# FrontPanel-IN14.net
KiCad netlist of a schematic drawn in EAGLE
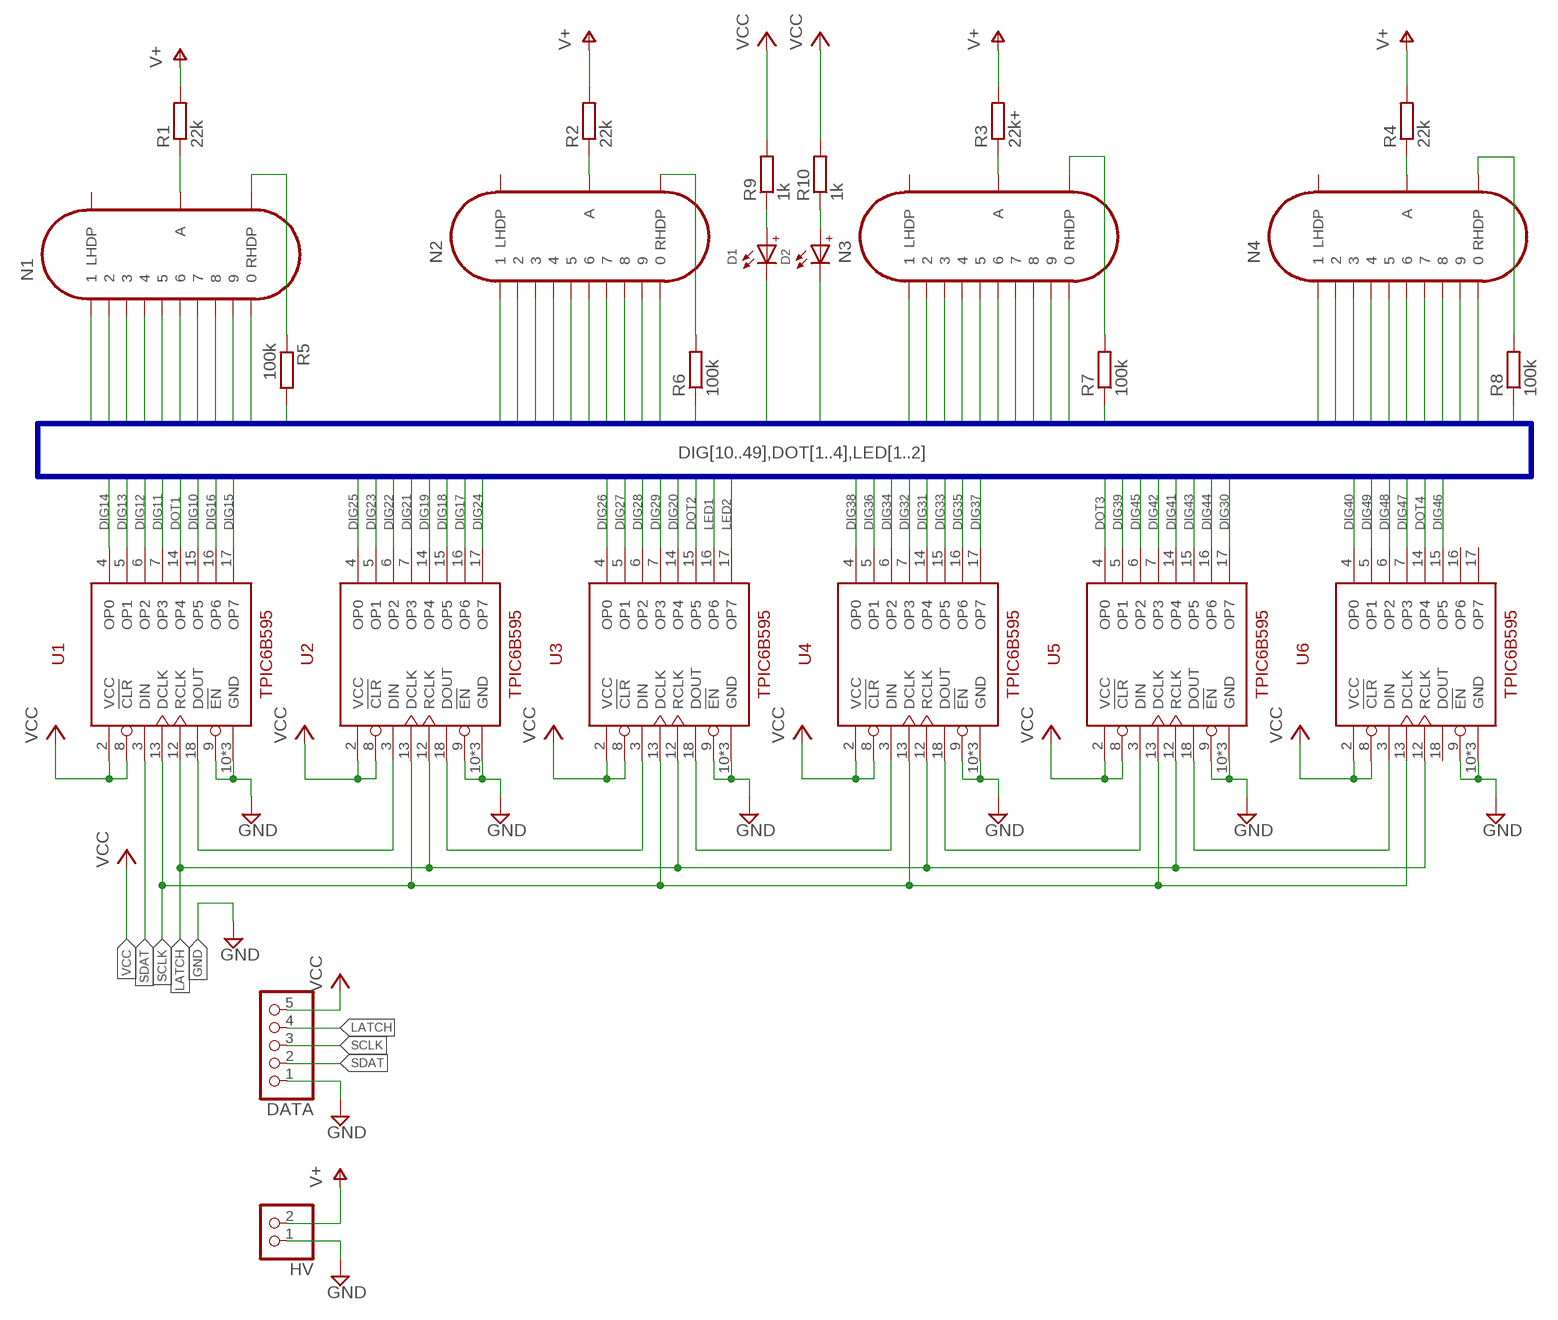
[diagram p0: schematic, sheet 1]

(export (version "E")
  (design (tool "Eeschema 10.0.6"))
  (components
    (comp (ref "D1")
      (value "RED/AMBER")
      (footprint "eagle-import:WL-SITW_154141XXBA210")
      (libsource (lib "eagle-import") (part "WL-SITW_3528_15414185BA210"))
    )
    (comp (ref "D2")
      (value "RED/AMBER")
      (footprint "eagle-import:WL-SITW_154141XXBA210")
      (libsource (lib "eagle-import") (part "WL-SITW_3528_15414185BA210"))
    )
    (comp (ref "DATA")
      (value ".1\" Header")
      (footprint "eagle-import:1X05")
      (libsource (lib "eagle-import") (part "PINHD-1X5"))
    )
    (comp (ref "HV")
      (value ".1\" Header")
      (footprint "eagle-import:1X02")
      (libsource (lib "eagle-import") (part "PINHD-1X2"))
    )
    (comp (ref "N1")
      (value "IN-14")
      (footprint "eagle-import:IN-14")
      (libsource (lib "eagle-import") (part "IN-14"))
    )
    (comp (ref "N2")
      (value "IN-14")
      (footprint "eagle-import:IN-14")
      (libsource (lib "eagle-import") (part "IN-14"))
    )
    (comp (ref "N3")
      (value "IN-14")
      (footprint "eagle-import:IN-14")
      (libsource (lib "eagle-import") (part "IN-14"))
    )
    (comp (ref "N4")
      (value "IN-14")
      (footprint "eagle-import:IN-14")
      (libsource (lib "eagle-import") (part "IN-14"))
    )
    (comp (ref "R1")
      (value "22k")
      (footprint "eagle-import:0207_10")
      (libsource (lib "eagle-import") (part "R-EU_0207/10"))
    )
    (comp (ref "R2")
      (value "22k")
      (footprint "eagle-import:0207_10")
      (libsource (lib "eagle-import") (part "R-EU_0207/10"))
    )
    (comp (ref "R3")
      (value "22k+")
      (footprint "eagle-import:0207_10")
      (libsource (lib "eagle-import") (part "R-EU_0207/10"))
    )
    (comp (ref "R4")
      (value "22k")
      (footprint "eagle-import:0207_10")
      (libsource (lib "eagle-import") (part "R-EU_0207/10"))
    )
    (comp (ref "R5")
      (value "100k")
      (footprint "eagle-import:0207_10")
      (libsource (lib "eagle-import") (part "R-EU_0207/10"))
    )
    (comp (ref "R6")
      (value "100k")
      (footprint "eagle-import:0207_10")
      (libsource (lib "eagle-import") (part "R-EU_0207/10"))
    )
    (comp (ref "R7")
      (value "100k")
      (footprint "eagle-import:0207_10")
      (libsource (lib "eagle-import") (part "R-EU_0207/10"))
    )
    (comp (ref "R8")
      (value "100k")
      (footprint "eagle-import:0207_10")
      (libsource (lib "eagle-import") (part "R-EU_0207/10"))
    )
    (comp (ref "R9")
      (value "1k")
      (footprint "eagle-import:0207_10")
      (libsource (lib "eagle-import") (part "R-EU_0207/10"))
    )
    (comp (ref "R10")
      (value "1k")
      (footprint "eagle-import:0207_10")
      (libsource (lib "eagle-import") (part "R-EU_0207/10"))
    )
    (comp (ref "U1")
      (value "TPIC6B595N")
      (footprint "eagle-import:PDIP-20")
      (libsource (lib "eagle-import") (part "TPIC6B595N"))
    )
    (comp (ref "U2")
      (value "TPIC6B595N")
      (footprint "eagle-import:PDIP-20")
      (libsource (lib "eagle-import") (part "TPIC6B595N"))
    )
    (comp (ref "U3")
      (value "TPIC6B595N")
      (footprint "eagle-import:PDIP-20")
      (libsource (lib "eagle-import") (part "TPIC6B595N"))
    )
    (comp (ref "U4")
      (value "TPIC6B595N")
      (footprint "eagle-import:PDIP-20")
      (libsource (lib "eagle-import") (part "TPIC6B595N"))
    )
    (comp (ref "U5")
      (value "TPIC6B595N")
      (footprint "eagle-import:PDIP-20")
      (libsource (lib "eagle-import") (part "TPIC6B595N"))
    )
    (comp (ref "U6")
      (value "TPIC6B595N")
      (footprint "eagle-import:PDIP-20")
      (libsource (lib "eagle-import") (part "TPIC6B595N"))
    )
  )
  (nets
    (net (code "1") (name "/DIG10") (class "Default")
      (node (ref "N1") (pin "0") (pinfunction "0_0") (pintype "bidirectional"))
      (node (ref "U1") (pin "15") (pinfunction "OP5_15") (pintype "open_collector"))
    )
    (net (code "2") (name "/DIG11") (class "Default")
      (node (ref "N1") (pin "1") (pinfunction "1_1") (pintype "bidirectional"))
      (node (ref "U1") (pin "7") (pinfunction "OP3_7") (pintype "open_collector"))
    )
    (net (code "3") (name "/DIG12") (class "Default")
      (node (ref "N1") (pin "2") (pinfunction "2_2") (pintype "bidirectional"))
      (node (ref "U1") (pin "6") (pinfunction "OP2_6") (pintype "open_collector"))
    )
    (net (code "4") (name "/DIG13") (class "Default")
      (node (ref "N1") (pin "3") (pinfunction "3_3") (pintype "bidirectional"))
      (node (ref "U1") (pin "5") (pinfunction "OP1_5") (pintype "open_collector"))
    )
    (net (code "5") (name "/DIG14") (class "Default")
      (node (ref "N1") (pin "4") (pinfunction "4_4") (pintype "bidirectional"))
      (node (ref "U1") (pin "4") (pinfunction "OP0_4") (pintype "open_collector"))
    )
    (net (code "6") (name "/DIG15") (class "Default")
      (node (ref "N1") (pin "5") (pinfunction "5_5") (pintype "bidirectional"))
      (node (ref "U1") (pin "17") (pinfunction "OP7_17") (pintype "open_collector"))
    )
    (net (code "7") (name "/DIG16") (class "Default")
      (node (ref "N1") (pin "6") (pinfunction "6_6") (pintype "bidirectional"))
      (node (ref "U1") (pin "16") (pinfunction "OP6_16") (pintype "open_collector"))
    )
    (net (code "8") (name "/DIG17") (class "Default")
      (node (ref "N1") (pin "7") (pinfunction "7_7") (pintype "bidirectional"))
      (node (ref "U2") (pin "16") (pinfunction "OP6_16") (pintype "open_collector"))
    )
    (net (code "9") (name "/DIG18") (class "Default")
      (node (ref "N1") (pin "8") (pinfunction "8_8") (pintype "bidirectional"))
      (node (ref "U2") (pin "15") (pinfunction "OP5_15") (pintype "open_collector"))
    )
    (net (code "10") (name "/DIG19") (class "Default")
      (node (ref "N1") (pin "9") (pinfunction "9_9") (pintype "bidirectional"))
      (node (ref "U2") (pin "14") (pinfunction "OP4_14") (pintype "open_collector"))
    )
    (net (code "11") (name "/DIG20") (class "Default")
      (node (ref "N2") (pin "0") (pinfunction "0_0") (pintype "bidirectional"))
      (node (ref "U3") (pin "14") (pinfunction "OP4_14") (pintype "open_collector"))
    )
    (net (code "12") (name "/DIG21") (class "Default")
      (node (ref "N2") (pin "1") (pinfunction "1_1") (pintype "bidirectional"))
      (node (ref "U2") (pin "7") (pinfunction "OP3_7") (pintype "open_collector"))
    )
    (net (code "13") (name "/DIG22") (class "Default")
      (node (ref "N2") (pin "2") (pinfunction "2_2") (pintype "bidirectional"))
      (node (ref "U2") (pin "6") (pinfunction "OP2_6") (pintype "open_collector"))
    )
    (net (code "14") (name "/DIG23") (class "Default")
      (node (ref "N2") (pin "3") (pinfunction "3_3") (pintype "bidirectional"))
      (node (ref "U2") (pin "5") (pinfunction "OP1_5") (pintype "open_collector"))
    )
    (net (code "15") (name "/DIG24") (class "Default")
      (node (ref "N2") (pin "4") (pinfunction "4_4") (pintype "bidirectional"))
      (node (ref "U2") (pin "17") (pinfunction "OP7_17") (pintype "open_collector"))
    )
    (net (code "16") (name "/DIG25") (class "Default")
      (node (ref "N2") (pin "5") (pinfunction "5_5") (pintype "bidirectional"))
      (node (ref "U2") (pin "4") (pinfunction "OP0_4") (pintype "open_collector"))
    )
    (net (code "17") (name "/DIG26") (class "Default")
      (node (ref "N2") (pin "6") (pinfunction "6_6") (pintype "bidirectional"))
      (node (ref "U3") (pin "4") (pinfunction "OP0_4") (pintype "open_collector"))
    )
    (net (code "18") (name "/DIG27") (class "Default")
      (node (ref "N2") (pin "7") (pinfunction "7_7") (pintype "bidirectional"))
      (node (ref "U3") (pin "5") (pinfunction "OP1_5") (pintype "open_collector"))
    )
    (net (code "19") (name "/DIG28") (class "Default")
      (node (ref "N2") (pin "8") (pinfunction "8_8") (pintype "bidirectional"))
      (node (ref "U3") (pin "6") (pinfunction "OP2_6") (pintype "open_collector"))
    )
    (net (code "20") (name "/DIG29") (class "Default")
      (node (ref "N2") (pin "9") (pinfunction "9_9") (pintype "bidirectional"))
      (node (ref "U3") (pin "7") (pinfunction "OP3_7") (pintype "open_collector"))
    )
    (net (code "21") (name "/DIG30") (class "Default")
      (node (ref "N3") (pin "0") (pinfunction "0_0") (pintype "bidirectional"))
      (node (ref "U5") (pin "17") (pinfunction "OP7_17") (pintype "open_collector"))
    )
    (net (code "22") (name "/DIG31") (class "Default")
      (node (ref "N3") (pin "1") (pinfunction "1_1") (pintype "bidirectional"))
      (node (ref "U4") (pin "14") (pinfunction "OP4_14") (pintype "open_collector"))
    )
    (net (code "23") (name "/DIG32") (class "Default")
      (node (ref "N3") (pin "2") (pinfunction "2_2") (pintype "bidirectional"))
      (node (ref "U4") (pin "7") (pinfunction "OP3_7") (pintype "open_collector"))
    )
    (net (code "24") (name "/DIG33") (class "Default")
      (node (ref "N3") (pin "3") (pinfunction "3_3") (pintype "bidirectional"))
      (node (ref "U4") (pin "15") (pinfunction "OP5_15") (pintype "open_collector"))
    )
    (net (code "25") (name "/DIG34") (class "Default")
      (node (ref "N3") (pin "4") (pinfunction "4_4") (pintype "bidirectional"))
      (node (ref "U4") (pin "6") (pinfunction "OP2_6") (pintype "open_collector"))
    )
    (net (code "26") (name "/DIG35") (class "Default")
      (node (ref "N3") (pin "5") (pinfunction "5_5") (pintype "bidirectional"))
      (node (ref "U4") (pin "16") (pinfunction "OP6_16") (pintype "open_collector"))
    )
    (net (code "27") (name "/DIG36") (class "Default")
      (node (ref "N3") (pin "6") (pinfunction "6_6") (pintype "bidirectional"))
      (node (ref "U4") (pin "5") (pinfunction "OP1_5") (pintype "open_collector"))
    )
    (net (code "28") (name "/DIG37") (class "Default")
      (node (ref "N3") (pin "7") (pinfunction "7_7") (pintype "bidirectional"))
      (node (ref "U4") (pin "17") (pinfunction "OP7_17") (pintype "open_collector"))
    )
    (net (code "29") (name "/DIG38") (class "Default")
      (node (ref "N3") (pin "8") (pinfunction "8_8") (pintype "bidirectional"))
      (node (ref "U4") (pin "4") (pinfunction "OP0_4") (pintype "open_collector"))
    )
    (net (code "30") (name "/DIG39") (class "Default")
      (node (ref "N3") (pin "9") (pinfunction "9_9") (pintype "bidirectional"))
      (node (ref "U5") (pin "5") (pinfunction "OP1_5") (pintype "open_collector"))
    )
    (net (code "31") (name "/DIG40") (class "Default")
      (node (ref "N4") (pin "0") (pinfunction "0_0") (pintype "bidirectional"))
      (node (ref "U6") (pin "4") (pinfunction "OP0_4") (pintype "open_collector"))
    )
    (net (code "32") (name "/DIG41") (class "Default")
      (node (ref "N4") (pin "1") (pinfunction "1_1") (pintype "bidirectional"))
      (node (ref "U5") (pin "14") (pinfunction "OP4_14") (pintype "open_collector"))
    )
    (net (code "33") (name "/DIG42") (class "Default")
      (node (ref "N4") (pin "2") (pinfunction "2_2") (pintype "bidirectional"))
      (node (ref "U5") (pin "7") (pinfunction "OP3_7") (pintype "open_collector"))
    )
    (net (code "34") (name "/DIG43") (class "Default")
      (node (ref "N4") (pin "3") (pinfunction "3_3") (pintype "bidirectional"))
      (node (ref "U5") (pin "15") (pinfunction "OP5_15") (pintype "open_collector"))
    )
    (net (code "35") (name "/DIG44") (class "Default")
      (node (ref "N4") (pin "4") (pinfunction "4_4") (pintype "bidirectional"))
      (node (ref "U5") (pin "16") (pinfunction "OP6_16") (pintype "open_collector"))
    )
    (net (code "36") (name "/DIG45") (class "Default")
      (node (ref "N4") (pin "5") (pinfunction "5_5") (pintype "bidirectional"))
      (node (ref "U5") (pin "6") (pinfunction "OP2_6") (pintype "open_collector"))
    )
    (net (code "37") (name "/DIG46") (class "Default")
      (node (ref "N4") (pin "6") (pinfunction "6_6") (pintype "bidirectional"))
      (node (ref "U6") (pin "15") (pinfunction "OP5_15") (pintype "open_collector"))
    )
    (net (code "38") (name "/DIG47") (class "Default")
      (node (ref "N4") (pin "7") (pinfunction "7_7") (pintype "bidirectional"))
      (node (ref "U6") (pin "7") (pinfunction "OP3_7") (pintype "open_collector"))
    )
    (net (code "39") (name "/DIG48") (class "Default")
      (node (ref "N4") (pin "8") (pinfunction "8_8") (pintype "bidirectional"))
      (node (ref "U6") (pin "6") (pinfunction "OP2_6") (pintype "open_collector"))
    )
    (net (code "40") (name "/DIG49") (class "Default")
      (node (ref "N4") (pin "9") (pinfunction "9_9") (pintype "bidirectional"))
      (node (ref "U6") (pin "5") (pinfunction "OP1_5") (pintype "open_collector"))
    )
    (net (code "41") (name "/DOT1") (class "Default")
      (node (ref "R5") (pin "2") (pinfunction "2_2") (pintype "passive"))
      (node (ref "U1") (pin "14") (pinfunction "OP4_14") (pintype "open_collector"))
    )
    (net (code "42") (name "/DOT2") (class "Default")
      (node (ref "R6") (pin "1") (pinfunction "1_1") (pintype "passive"))
      (node (ref "U3") (pin "15") (pinfunction "OP5_15") (pintype "open_collector"))
    )
    (net (code "43") (name "/DOT3") (class "Default")
      (node (ref "R7") (pin "1") (pinfunction "1_1") (pintype "passive"))
      (node (ref "U5") (pin "4") (pinfunction "OP0_4") (pintype "open_collector"))
    )
    (net (code "44") (name "/DOT4") (class "Default")
      (node (ref "R8") (pin "1") (pinfunction "1_1") (pintype "passive"))
      (node (ref "U6") (pin "14") (pinfunction "OP4_14") (pintype "open_collector"))
    )
    (net (code "45") (name "/LED1") (class "Default")
      (node (ref "D1") (pin "2") (pinfunction "-_2") (pintype "passive"))
      (node (ref "U3") (pin "16") (pinfunction "OP6_16") (pintype "open_collector"))
    )
    (net (code "46") (name "/LED2") (class "Default")
      (node (ref "D2") (pin "2") (pinfunction "-_2") (pintype "passive"))
      (node (ref "U3") (pin "17") (pinfunction "OP7_17") (pintype "open_collector"))
    )
    (net (code "48") (name "GND") (class "Default")
      (node (ref "DATA") (pin "1") (pinfunction "1_1") (pintype "passive"))
      (node (ref "HV") (pin "1") (pinfunction "1_1") (pintype "passive"))
      (node (ref "U1") (pin "10") (pinfunction "GND_10") (pintype "power_in"))
      (node (ref "U1") (pin "11") (pinfunction "GND_11") (pintype "power_in"))
      (node (ref "U1") (pin "19") (pinfunction "GND_19") (pintype "power_in"))
      (node (ref "U1") (pin "9") (pinfunction "~{EN}_9") (pintype "input"))
      (node (ref "U2") (pin "10") (pinfunction "GND_10") (pintype "power_in"))
      (node (ref "U2") (pin "11") (pinfunction "GND_11") (pintype "power_in"))
      (node (ref "U2") (pin "19") (pinfunction "GND_19") (pintype "power_in"))
      (node (ref "U2") (pin "9") (pinfunction "~{EN}_9") (pintype "input"))
      (node (ref "U3") (pin "10") (pinfunction "GND_10") (pintype "power_in"))
      (node (ref "U3") (pin "11") (pinfunction "GND_11") (pintype "power_in"))
      (node (ref "U3") (pin "19") (pinfunction "GND_19") (pintype "power_in"))
      (node (ref "U3") (pin "9") (pinfunction "~{EN}_9") (pintype "input"))
      (node (ref "U4") (pin "10") (pinfunction "GND_10") (pintype "power_in"))
      (node (ref "U4") (pin "11") (pinfunction "GND_11") (pintype "power_in"))
      (node (ref "U4") (pin "19") (pinfunction "GND_19") (pintype "power_in"))
      (node (ref "U4") (pin "9") (pinfunction "~{EN}_9") (pintype "input"))
      (node (ref "U5") (pin "10") (pinfunction "GND_10") (pintype "power_in"))
      (node (ref "U5") (pin "11") (pinfunction "GND_11") (pintype "power_in"))
      (node (ref "U5") (pin "19") (pinfunction "GND_19") (pintype "power_in"))
      (node (ref "U5") (pin "9") (pinfunction "~{EN}_9") (pintype "input"))
      (node (ref "U6") (pin "10") (pinfunction "GND_10") (pintype "power_in"))
      (node (ref "U6") (pin "11") (pinfunction "GND_11") (pintype "power_in"))
      (node (ref "U6") (pin "19") (pinfunction "GND_19") (pintype "power_in"))
      (node (ref "U6") (pin "9") (pinfunction "~{EN}_9") (pintype "input"))
    )
    (net (code "49") (name "LATCH") (class "Default")
      (node (ref "DATA") (pin "4") (pinfunction "4_4") (pintype "passive"))
      (node (ref "U1") (pin "12") (pinfunction "RCLK_12") (pintype "input"))
      (node (ref "U2") (pin "12") (pinfunction "RCLK_12") (pintype "input"))
      (node (ref "U3") (pin "12") (pinfunction "RCLK_12") (pintype "input"))
      (node (ref "U4") (pin "12") (pinfunction "RCLK_12") (pintype "input"))
      (node (ref "U5") (pin "12") (pinfunction "RCLK_12") (pintype "input"))
      (node (ref "U6") (pin "12") (pinfunction "RCLK_12") (pintype "input"))
    )
    (net (code "50") (name "Net-(D1-+)") (class "Default")
      (node (ref "D1") (pin "1") (pinfunction "+_1") (pintype "passive"))
      (node (ref "R9") (pin "1") (pinfunction "1_1") (pintype "passive"))
    )
    (net (code "51") (name "Net-(D2-+)") (class "Default")
      (node (ref "D2") (pin "1") (pinfunction "+_1") (pintype "passive"))
      (node (ref "R10") (pin "1") (pinfunction "1_1") (pintype "passive"))
    )
    (net (code "52") (name "Net-(N1-PadA)") (class "Default")
      (node (ref "N1") (pin "A") (pinfunction "A_A") (pintype "bidirectional"))
      (node (ref "R1") (pin "1") (pinfunction "1_1") (pintype "passive"))
    )
    (net (code "53") (name "Net-(N1-PadRHDP)") (class "Default")
      (node (ref "N1") (pin "RHDP") (pinfunction "RHDP_RHDP") (pintype "bidirectional"))
      (node (ref "R5") (pin "1") (pinfunction "1_1") (pintype "passive"))
    )
    (net (code "54") (name "Net-(N2-PadA)") (class "Default")
      (node (ref "N2") (pin "A") (pinfunction "A_A") (pintype "bidirectional"))
      (node (ref "R2") (pin "1") (pinfunction "1_1") (pintype "passive"))
    )
    (net (code "55") (name "Net-(N2-PadRHDP)") (class "Default")
      (node (ref "N2") (pin "RHDP") (pinfunction "RHDP_RHDP") (pintype "bidirectional"))
      (node (ref "R6") (pin "2") (pinfunction "2_2") (pintype "passive"))
    )
    (net (code "56") (name "Net-(N3-PadA)") (class "Default")
      (node (ref "N3") (pin "A") (pinfunction "A_A") (pintype "bidirectional"))
      (node (ref "R3") (pin "1") (pinfunction "1_1") (pintype "passive"))
    )
    (net (code "57") (name "Net-(N3-PadRHDP)") (class "Default")
      (node (ref "N3") (pin "RHDP") (pinfunction "RHDP_RHDP") (pintype "bidirectional"))
      (node (ref "R7") (pin "2") (pinfunction "2_2") (pintype "passive"))
    )
    (net (code "58") (name "Net-(N4-PadA)") (class "Default")
      (node (ref "N4") (pin "A") (pinfunction "A_A") (pintype "bidirectional"))
      (node (ref "R4") (pin "1") (pinfunction "1_1") (pintype "passive"))
    )
    (net (code "59") (name "Net-(N4-PadRHDP)") (class "Default")
      (node (ref "N4") (pin "RHDP") (pinfunction "RHDP_RHDP") (pintype "bidirectional"))
      (node (ref "R8") (pin "2") (pinfunction "2_2") (pintype "passive"))
    )
    (net (code "60") (name "Net-(U1-DOUT)") (class "Default")
      (node (ref "U1") (pin "18") (pinfunction "DOUT_18") (pintype "output"))
      (node (ref "U2") (pin "3") (pinfunction "DIN_3") (pintype "input"))
    )
    (net (code "61") (name "Net-(U2-DOUT)") (class "Default")
      (node (ref "U2") (pin "18") (pinfunction "DOUT_18") (pintype "output"))
      (node (ref "U3") (pin "3") (pinfunction "DIN_3") (pintype "input"))
    )
    (net (code "62") (name "Net-(U3-DOUT)") (class "Default")
      (node (ref "U3") (pin "18") (pinfunction "DOUT_18") (pintype "output"))
      (node (ref "U4") (pin "3") (pinfunction "DIN_3") (pintype "input"))
    )
    (net (code "63") (name "Net-(U4-DOUT)") (class "Default")
      (node (ref "U4") (pin "18") (pinfunction "DOUT_18") (pintype "output"))
      (node (ref "U5") (pin "3") (pinfunction "DIN_3") (pintype "input"))
    )
    (net (code "64") (name "Net-(U5-DOUT)") (class "Default")
      (node (ref "U5") (pin "18") (pinfunction "DOUT_18") (pintype "output"))
      (node (ref "U6") (pin "3") (pinfunction "DIN_3") (pintype "input"))
    )
    (net (code "65") (name "SCLK") (class "Default")
      (node (ref "DATA") (pin "3") (pinfunction "3_3") (pintype "passive"))
      (node (ref "U1") (pin "13") (pinfunction "DCLK_13") (pintype "input"))
      (node (ref "U2") (pin "13") (pinfunction "DCLK_13") (pintype "input"))
      (node (ref "U3") (pin "13") (pinfunction "DCLK_13") (pintype "input"))
      (node (ref "U4") (pin "13") (pinfunction "DCLK_13") (pintype "input"))
      (node (ref "U5") (pin "13") (pinfunction "DCLK_13") (pintype "input"))
      (node (ref "U6") (pin "13") (pinfunction "DCLK_13") (pintype "input"))
    )
    (net (code "66") (name "SDAT") (class "Default")
      (node (ref "DATA") (pin "2") (pinfunction "2_2") (pintype "passive"))
      (node (ref "U1") (pin "3") (pinfunction "DIN_3") (pintype "input"))
    )
    (net (code "67") (name "V+") (class "Default")
      (node (ref "HV") (pin "2") (pinfunction "2_2") (pintype "passive"))
      (node (ref "R1") (pin "2") (pinfunction "2_2") (pintype "passive"))
      (node (ref "R2") (pin "2") (pinfunction "2_2") (pintype "passive"))
      (node (ref "R3") (pin "2") (pinfunction "2_2") (pintype "passive"))
      (node (ref "R4") (pin "2") (pinfunction "2_2") (pintype "passive"))
    )
    (net (code "68") (name "VCC") (class "Default")
      (node (ref "DATA") (pin "5") (pinfunction "5_5") (pintype "passive"))
      (node (ref "R10") (pin "2") (pinfunction "2_2") (pintype "passive"))
      (node (ref "R9") (pin "2") (pinfunction "2_2") (pintype "passive"))
      (node (ref "U1") (pin "2") (pinfunction "VCC_2") (pintype "power_in"))
      (node (ref "U1") (pin "8") (pinfunction "~{CLR}_8") (pintype "input"))
      (node (ref "U2") (pin "2") (pinfunction "VCC_2") (pintype "power_in"))
      (node (ref "U2") (pin "8") (pinfunction "~{CLR}_8") (pintype "input"))
      (node (ref "U3") (pin "2") (pinfunction "VCC_2") (pintype "power_in"))
      (node (ref "U3") (pin "8") (pinfunction "~{CLR}_8") (pintype "input"))
      (node (ref "U4") (pin "2") (pinfunction "VCC_2") (pintype "power_in"))
      (node (ref "U4") (pin "8") (pinfunction "~{CLR}_8") (pintype "input"))
      (node (ref "U5") (pin "2") (pinfunction "VCC_2") (pintype "power_in"))
      (node (ref "U5") (pin "8") (pinfunction "~{CLR}_8") (pintype "input"))
      (node (ref "U6") (pin "2") (pinfunction "VCC_2") (pintype "power_in"))
      (node (ref "U6") (pin "8") (pinfunction "~{CLR}_8") (pintype "input"))
    )
    (net (code "69") (name "unconnected-(N1-PadLHDP)") (class "Default")
      (node (ref "N1") (pin "LHDP") (pinfunction "LHDP_LHDP") (pintype "bidirectional"))
    )
    (net (code "70") (name "unconnected-(N2-PadLHDP)") (class "Default")
      (node (ref "N2") (pin "LHDP") (pinfunction "LHDP_LHDP") (pintype "bidirectional"))
    )
    (net (code "71") (name "unconnected-(N3-PadLHDP)") (class "Default")
      (node (ref "N3") (pin "LHDP") (pinfunction "LHDP_LHDP") (pintype "bidirectional"))
    )
    (net (code "72") (name "unconnected-(N4-PadLHDP)") (class "Default")
      (node (ref "N4") (pin "LHDP") (pinfunction "LHDP_LHDP") (pintype "bidirectional"))
    )
    (net (code "73") (name "unconnected-(U6-DOUT-Pad18)") (class "Default")
      (node (ref "U6") (pin "18") (pinfunction "DOUT_18") (pintype "output"))
    )
    (net (code "74") (name "unconnected-(U6-OP6-Pad16)") (class "Default")
      (node (ref "U6") (pin "16") (pinfunction "OP6_16") (pintype "open_collector"))
    )
    (net (code "75") (name "unconnected-(U6-OP7-Pad17)") (class "Default")
      (node (ref "U6") (pin "17") (pinfunction "OP7_17") (pintype "open_collector"))
    )
  )
)
